# placasensores.net
KiCad netlist of a schematic drawn in EAGLE
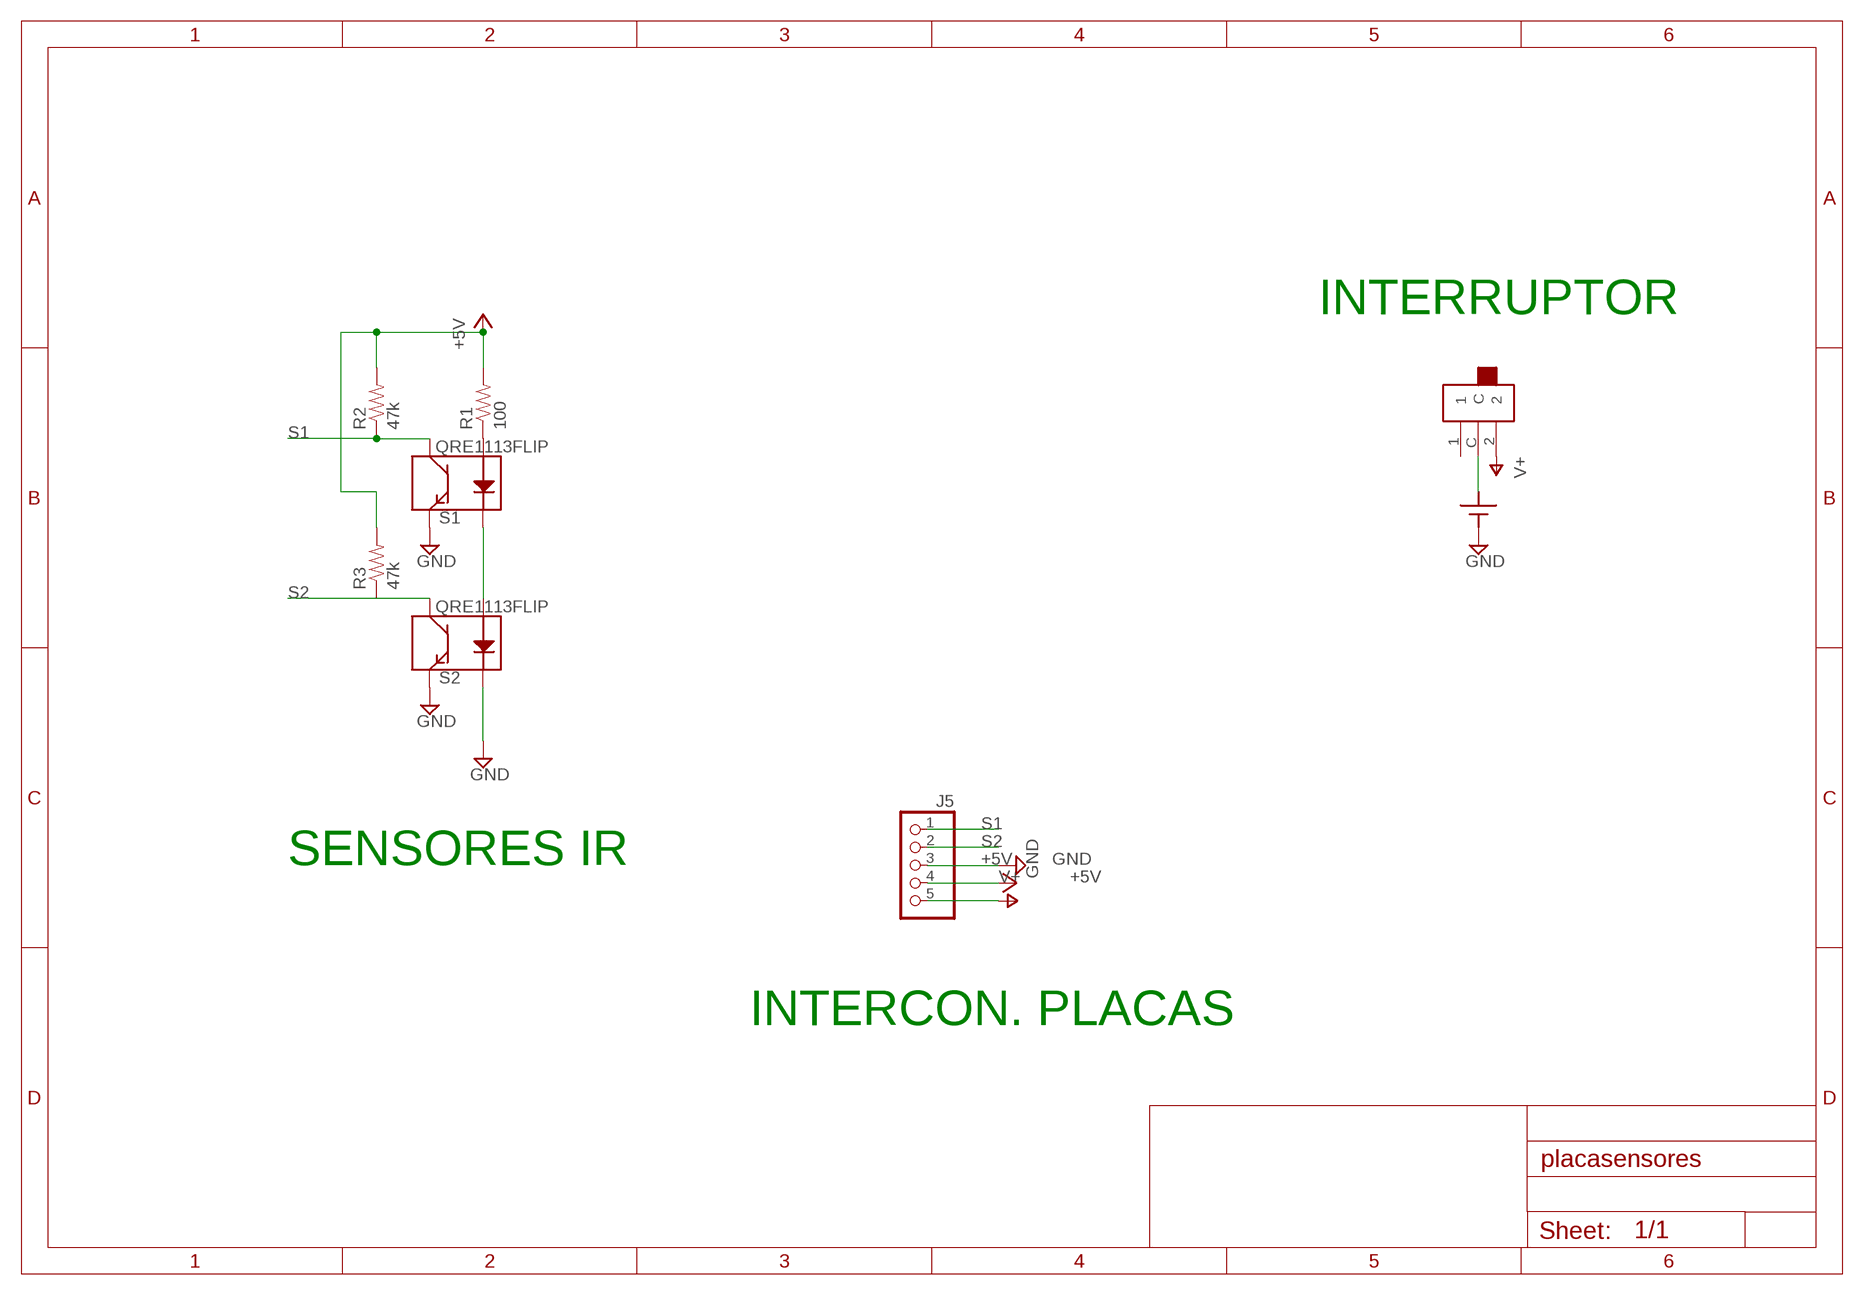
[diagram p0: schematic, sheet 1]

(export (version "E")
  (design (tool "Eeschema 10.0.6"))
  (components
    (comp (ref "J5")
      (value "PINHD-1X5")
      (footprint "eagle-import:1X05")
      (libsource (lib "eagle-import") (part "PINHD-1X5"))
    )
    (comp (ref "R1")
      (value "100")
      (footprint "eagle-import:1206")
      (libsource (lib "eagle-import") (part "RESISTOR1206"))
    )
    (comp (ref "R2")
      (value "47k")
      (footprint "eagle-import:1206")
      (libsource (lib "eagle-import") (part "RESISTOR1206"))
    )
    (comp (ref "R3")
      (value "47k")
      (footprint "eagle-import:1206")
      (libsource (lib "eagle-import") (part "RESISTOR1206"))
    )
    (comp (ref "S1")
      (value "QRE1113FLIP")
      (footprint "eagle-import:QRE1113GR_HOLE")
      (libsource (lib "eagle-import") (part "QRE1113FLIP"))
    )
    (comp (ref "S2")
      (value "QRE1113FLIP")
      (footprint "eagle-import:QRE1113GR_HOLE")
      (libsource (lib "eagle-import") (part "QRE1113FLIP"))
    )
    (comp (ref "SW1")
      (value "SK-12D07G3")
      (footprint "eagle-import:SK-12D07G3")
      (libsource (lib "eagle-import") (part "SK-12D07G3"))
    )
    (comp (ref "U$3")
      (value "5XAA")
      (footprint "eagle-import:5XAAHOLDER")
      (libsource (lib "eagle-import") (part "5XAA"))
    )
  )
  (nets
    (net (code "1") (name "+5V") (class "Default")
      (node (ref "J5") (pin "4") (pinfunction "4_4") (pintype "passive"))
      (node (ref "R1") (pin "2") (pinfunction "2_2") (pintype "passive"))
      (node (ref "R2") (pin "2") (pinfunction "2_2") (pintype "passive"))
      (node (ref "R3") (pin "2") (pinfunction "2_2") (pintype "passive"))
    )
    (net (code "2") (name "/S1") (class "Default")
      (node (ref "J5") (pin "1") (pinfunction "1_1") (pintype "passive"))
      (node (ref "R2") (pin "1") (pinfunction "1_1") (pintype "passive"))
      (node (ref "S1") (pin "C") (pinfunction "C_C") (pintype "bidirectional"))
    )
    (net (code "3") (name "/S2") (class "Default")
      (node (ref "J5") (pin "2") (pinfunction "2_2") (pintype "passive"))
      (node (ref "R3") (pin "1") (pinfunction "1_1") (pintype "passive"))
      (node (ref "S2") (pin "C") (pinfunction "C_C") (pintype "bidirectional"))
    )
    (net (code "4") (name "GND") (class "Default")
      (node (ref "J5") (pin "3") (pinfunction "3_3") (pintype "passive"))
      (node (ref "S1") (pin "E") (pinfunction "E_E") (pintype "bidirectional"))
      (node (ref "S2") (pin "E") (pinfunction "E_E") (pintype "bidirectional"))
      (node (ref "S2") (pin "K") (pinfunction "K_K") (pintype "bidirectional"))
      (node (ref "U$3") (pin "P$2") (pinfunction "P$2_P$2") (pintype "bidirectional"))
    )
    (net (code "5") (name "Net-(R1-Pad1)") (class "Default")
      (node (ref "R1") (pin "1") (pinfunction "1_1") (pintype "passive"))
      (node (ref "S1") (pin "A") (pinfunction "A_A") (pintype "bidirectional"))
    )
    (net (code "6") (name "Net-(S1-PadK)") (class "Default")
      (node (ref "S1") (pin "K") (pinfunction "K_K") (pintype "bidirectional"))
      (node (ref "S2") (pin "A") (pinfunction "A_A") (pintype "bidirectional"))
    )
    (net (code "7") (name "Net-(SW1-PadC)") (class "Default")
      (node (ref "SW1") (pin "C") (pinfunction "C_C") (pintype "bidirectional"))
      (node (ref "U$3") (pin "P$1") (pinfunction "P$1_P$1") (pintype "bidirectional"))
    )
    (net (code "8") (name "V+") (class "Default")
      (node (ref "J5") (pin "5") (pinfunction "5_5") (pintype "passive"))
      (node (ref "SW1") (pin "2") (pinfunction "2_2") (pintype "bidirectional"))
    )
    (net (code "9") (name "unconnected-(SW1-Pad1)") (class "Default")
      (node (ref "SW1") (pin "1") (pinfunction "1_1") (pintype "bidirectional"))
    )
  )
)
